# 5V_Buck_Converter.net
KiCad netlist of a schematic drawn in Altium Designer
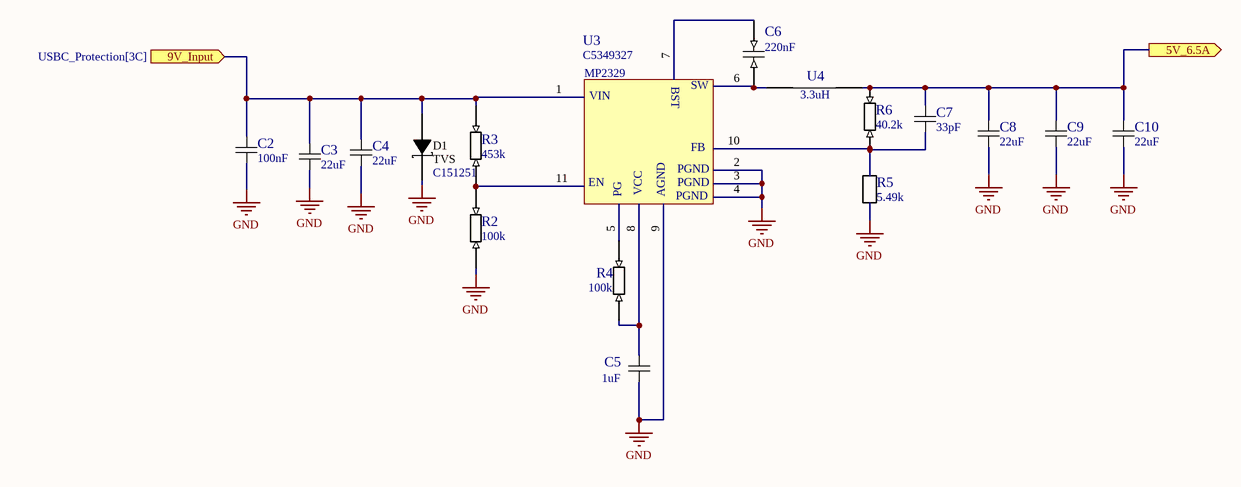
[diagram p0: 5V Buck Converter.SchDoc]

(export (version "E")
  (design (tool "Eeschema 10.0.6"))
  (components
    (comp (ref "C2")
      (value "100nF")
      (footprint "C0603")
      (description "C0603X7R104K250NT")
      (fields (field (name "SOURCE") "LCSC"))
      (libsource (lib "C466768") (part "C0603X7R104K250NT"))
    )
    (comp (ref "C3")
      (value "22uF")
      (footprint "C0805")
      (description "22uF ±20% 25V Ceramic Capacitor X5R 0805")
      (fields (field (name "Comment") "CL21A226MAQNNNE") (field (name "SOURCE") "LCSC"))
      (libsource (lib "C45783") (part "CL21A226MAQNNNE"))
    )
    (comp (ref "C4")
      (value "22uF")
      (footprint "C0805")
      (description "22uF ±20% 25V Ceramic Capacitor X5R 0805")
      (fields (field (name "Comment") "CL21A226MAQNNNE") (field (name "SOURCE") "LCSC"))
      (libsource (lib "C45783") (part "CL21A226MAQNNNE"))
    )
    (comp (ref "C5")
      (value "1uF")
      (footprint "C0603")
      (description "1uF ±10% 50V Ceramic Capacitor X5R 0603")
      (fields (field (name "Comment") "CL10A105KB8NNNC") (field (name "SOURCE") "LCSC"))
      (libsource (lib "C15849") (part "CL10A105KB8NNNC"))
    )
    (comp (ref "C6")
      (value "220nF")
      (footprint "C0603")
      (description "220nF ±10% 25V Ceramic Capacitor X7R 0603")
      (fields (field (name "Comment") "CL10B224KA8NNNC") (field (name "SOURCE") "LCSC"))
      (libsource (lib "C21120") (part "CL10B224KA8NNNC"))
    )
    (comp (ref "C7")
      (value "33pF")
      (footprint "C0603")
      (description "33pF C0G ±1% 50V 0603 Ceramic Capacitors")
      (fields (field (name "Comment") "TCC0603COG330F500CT") (field (name "SOURCE") "LCSC"))
      (libsource (lib "C48543706") (part "TCC0603COG330F500CT"))
    )
    (comp (ref "C8")
      (value "22uF")
      (footprint "C0805")
      (description "22uF ±20% 25V Ceramic Capacitor X5R 0805")
      (fields (field (name "Comment") "CL21A226MAQNNNE") (field (name "SOURCE") "LCSC"))
      (libsource (lib "C45783") (part "CL21A226MAQNNNE"))
    )
    (comp (ref "C9")
      (value "22uF")
      (footprint "C0805")
      (description "22uF ±20% 25V Ceramic Capacitor X5R 0805")
      (fields (field (name "Comment") "CL21A226MAQNNNE") (field (name "SOURCE") "LCSC"))
      (libsource (lib "C45783") (part "CL21A226MAQNNNE"))
    )
    (comp (ref "C10")
      (value "22uF")
      (footprint "C0805")
      (description "22uF ±20% 25V Ceramic Capacitor X5R 0805")
      (fields (field (name "Comment") "CL21A226MAQNNNE") (field (name "SOURCE") "LCSC"))
      (libsource (lib "C45783") (part "CL21A226MAQNNNE"))
    )
    (comp (ref "D1")
      (value "TVS")
      (footprint "SMB_L4.6-W3.6-LS5.3-RD")
      (description "21.5VC Clamp 28A@10/1000us Ipp TVS DIODE DO-214AA")
      (fields (field (name "NAME") "C151251") (field (name "SOURCE") "LCSC"))
      (libsource (lib "C151251") (part "SMBJ12A_C151251"))
    )
    (comp (ref "R2")
      (value "100k")
      (footprint "R0603")
      (description "100kÎ© Â±1% 100mW 0603 Thick Film Resistor")
      (fields (field (name "Comment") "0603WAF1003T5E") (field (name "SOURCE") "LCSC"))
      (libsource (lib "C25803") (part "0603WAF1003T5E"))
    )
    (comp (ref "R3")
      (value "453k")
      (footprint "R0603")
      (description "453kÎ© Â±1% 100mW 0603 Thick Film Resistor")
      (fields (field (name "Comment") "0603WAF4533T5E") (field (name "SOURCE") "LCSC"))
      (libsource (lib "C25818") (part "0603WAF4533T5E"))
    )
    (comp (ref "R4")
      (value "100k")
      (footprint "R0603")
      (description "100kÎ© Â±1% 100mW 0603 Thick Film Resistor")
      (fields (field (name "Comment") "0603WAF1003T5E") (field (name "SOURCE") "LCSC"))
      (libsource (lib "C25803") (part "0603WAF1003T5E"))
    )
    (comp (ref "R5")
      (value "5.49k")
      (footprint "R0603")
      (description "5.49kÎ© 100mW 75V Thick Film Resistor Â±100ppm/â„ƒ Â±1% 0603 Chip Resistor - Surface Mount")
      (fields (field (name "Comment") "FRQ0603F5491TS") (field (name "SOURCE") "LCSC"))
      (libsource (lib "C54102278") (part "FRQ0603F5491TS"))
    )
    (comp (ref "R6")
      (value "40.2k")
      (footprint "R0603")
      (description "40.2kÎ© Â±1% 100mW 0603 Thick Film Resistor")
      (fields (field (name "Comment") "0603WAF4022T5E") (field (name "SOURCE") "LCSC"))
      (libsource (lib "C12447") (part "0603WAF4022T5E"))
    )
    (comp (ref "U3")
      (value "MP2329GG-Z")
      (footprint "QFN-11_L2.0-W2.0-P0.50_MP2384CGG-Z")
      (fields (field (name "NAME") "C5349327") (field (name "SOURCE") "LCSC"))
      (libsource (lib "C5349327") (part "MP2329GG-Z"))
    )
    (comp (ref "U4")
      (value "3.3uH")
      (footprint "IND-SMD_L9.2-W8.0")
      (description "10A 3.3uH ±20% 15A Molded inductor SMD,9.2x8mm Fixed Inductors")
      (fields (field (name "Comment") "CYA0850-3.3UH") (field (name "SOURCE") "LCSC"))
      (libsource (lib "C19268642") (part "CYA0850-3.3UH"))
    )
  )
  (nets
    (net (code "1") (name "/5V_6.5A") (class "Default")
      (node (ref "C10") (pin "1") (pinfunction "1_1") (pintype "passive"))
      (node (ref "C7") (pin "2") (pinfunction "2_2") (pintype "passive"))
      (node (ref "C8") (pin "1") (pinfunction "1_1") (pintype "passive"))
      (node (ref "C9") (pin "1") (pinfunction "1_1") (pintype "passive"))
      (node (ref "R6") (pin "2") (pinfunction "2_2") (pintype "input"))
      (node (ref "U4") (pin "2") (pinfunction "2_2") (pintype "passive"))
    )
    (net (code "2") (name "/9V_Input") (class "Default")
      (node (ref "C2") (pin "2") (pinfunction "2_2") (pintype "passive"))
      (node (ref "C3") (pin "2") (pinfunction "2_2") (pintype "passive"))
      (node (ref "C4") (pin "2") (pinfunction "2_2") (pintype "passive"))
      (node (ref "D1") (pin "2") (pinfunction "A_2") (pintype "passive"))
      (node (ref "R3") (pin "2") (pinfunction "2_2") (pintype "input"))
      (node (ref "U3") (pin "1") (pinfunction "1_1") (pintype "passive"))
    )
    (net (code "3") (name "GND") (class "Default")
      (node (ref "C10") (pin "2") (pinfunction "2_2") (pintype "passive"))
      (node (ref "C2") (pin "1") (pinfunction "1_1") (pintype "passive"))
      (node (ref "C3") (pin "1") (pinfunction "1_1") (pintype "passive"))
      (node (ref "C4") (pin "1") (pinfunction "1_1") (pintype "passive"))
      (node (ref "C5") (pin "1") (pinfunction "1_1") (pintype "passive"))
      (node (ref "C8") (pin "2") (pinfunction "2_2") (pintype "passive"))
      (node (ref "C9") (pin "2") (pinfunction "2_2") (pintype "passive"))
      (node (ref "D1") (pin "1") (pinfunction "K_1") (pintype "passive"))
      (node (ref "R2") (pin "1") (pinfunction "1_1") (pintype "input"))
      (node (ref "R5") (pin "1") (pinfunction "1_1") (pintype "passive"))
      (node (ref "U3") (pin "2") (pinfunction "2_2") (pintype "passive"))
      (node (ref "U3") (pin "3") (pinfunction "3_3") (pintype "passive"))
      (node (ref "U3") (pin "4") (pinfunction "4_4") (pintype "passive"))
      (node (ref "U3") (pin "9") (pinfunction "9_9") (pintype "passive"))
    )
    (net (code "4") (name "Net-(C5-Pad2)") (class "Default")
      (node (ref "C5") (pin "2") (pinfunction "2_2") (pintype "passive"))
      (node (ref "R4") (pin "1") (pinfunction "1_1") (pintype "input"))
      (node (ref "U3") (pin "8") (pinfunction "8_8") (pintype "passive"))
    )
    (net (code "5") (name "Net-(C6-Pad1)") (class "Default")
      (node (ref "C6") (pin "1") (pinfunction "1_1") (pintype "input"))
      (node (ref "U3") (pin "6") (pinfunction "6_6") (pintype "passive"))
      (node (ref "U4") (pin "1") (pinfunction "1_1") (pintype "passive"))
    )
    (net (code "6") (name "Net-(C6-Pad2)") (class "Default")
      (node (ref "C6") (pin "2") (pinfunction "2_2") (pintype "input"))
      (node (ref "U3") (pin "7") (pinfunction "7_7") (pintype "passive"))
    )
    (net (code "7") (name "Net-(C7-Pad1)") (class "Default")
      (node (ref "C7") (pin "1") (pinfunction "1_1") (pintype "passive"))
      (node (ref "R5") (pin "2") (pinfunction "2_2") (pintype "passive"))
      (node (ref "R6") (pin "1") (pinfunction "1_1") (pintype "input"))
      (node (ref "U3") (pin "10") (pinfunction "10_10") (pintype "passive"))
    )
    (net (code "8") (name "Net-(R2-Pad2)") (class "Default")
      (node (ref "R2") (pin "2") (pinfunction "2_2") (pintype "input"))
      (node (ref "R3") (pin "1") (pinfunction "1_1") (pintype "input"))
      (node (ref "U3") (pin "11") (pinfunction "11_11") (pintype "passive"))
    )
    (net (code "9") (name "Net-(R4-Pad2)") (class "Default")
      (node (ref "R4") (pin "2") (pinfunction "2_2") (pintype "input"))
      (node (ref "U3") (pin "5") (pinfunction "5_5") (pintype "passive"))
    )
  )
)
